# Sheet_FT4232_USB.net
KiCad netlist of a schematic drawn in Altium Designer
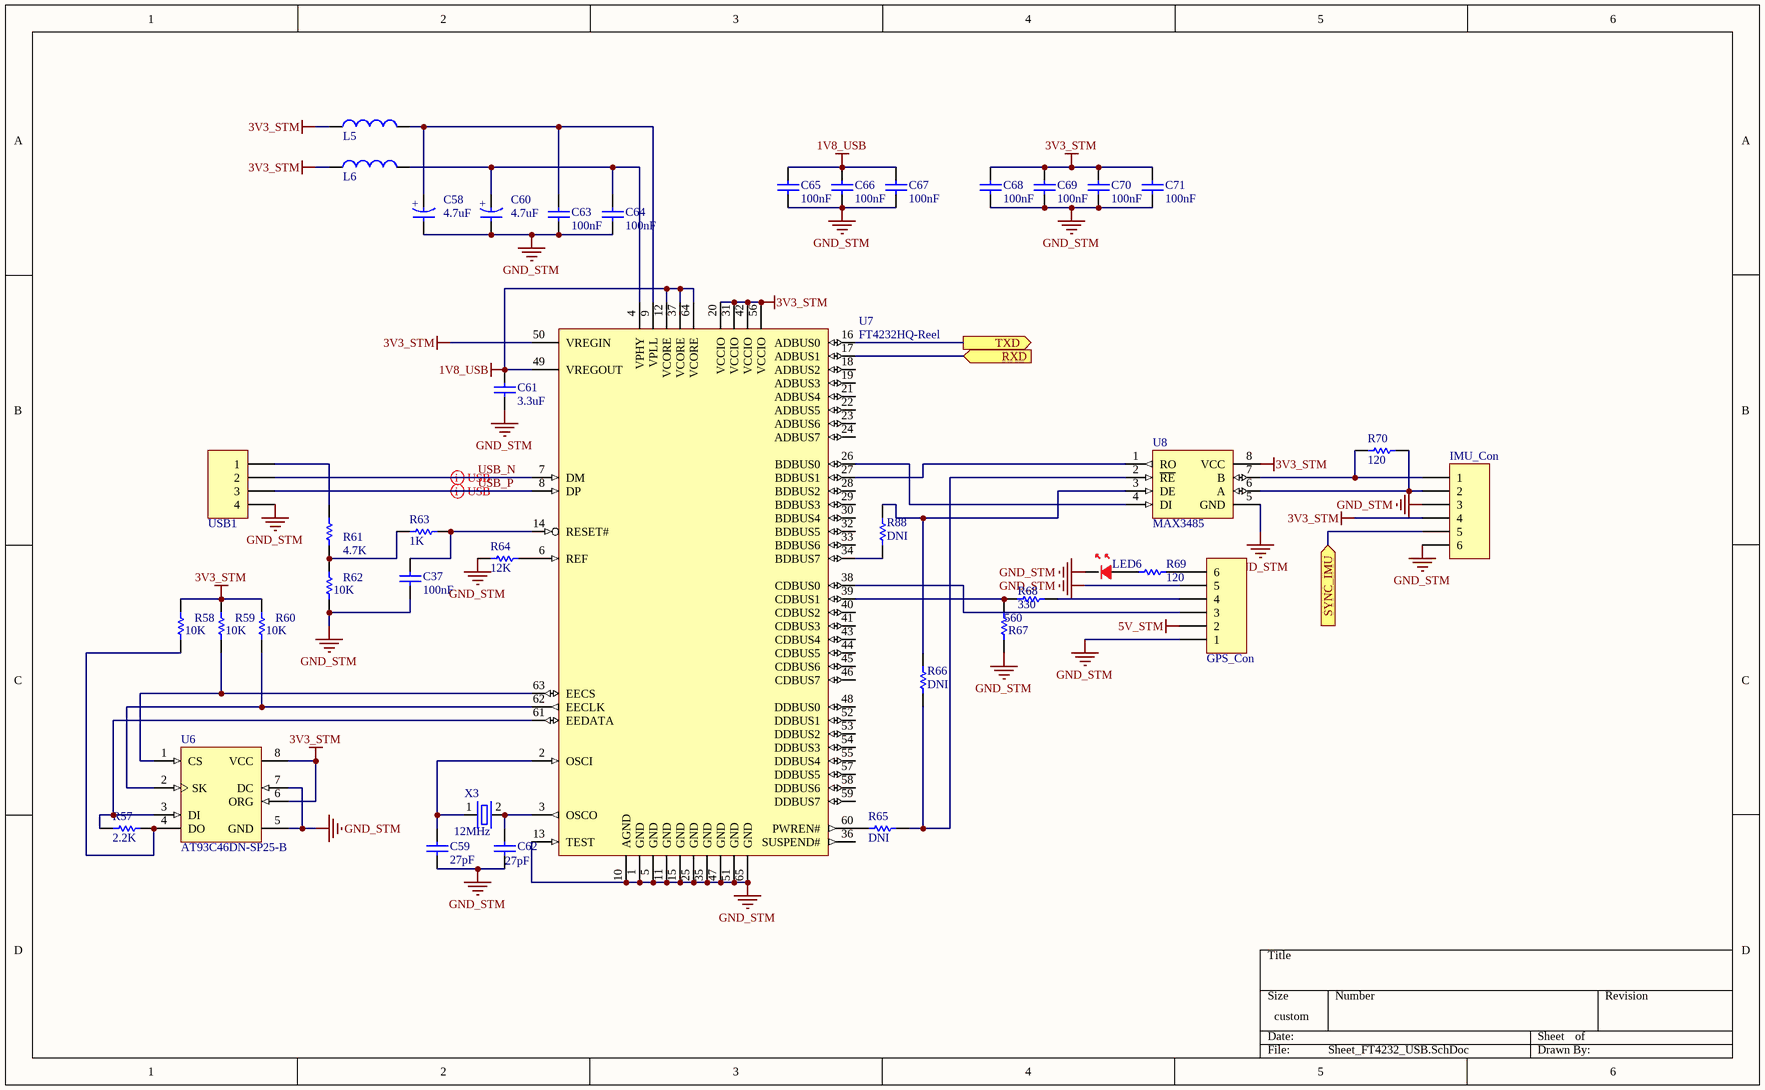
[diagram p0: Sheet_FT4232_USB.SchDoc]

(export (version "E")
  (design (tool "Eeschema 10.0.6"))
  (components
    (comp (ref "C37")
      (value "100nF")
      (footprint "ARPG_PCB_LIB:1608[0603]")
      (description "Capacitor")
      (libsource (lib "AlmaLib1") (part "Cap_BP"))
    )
    (comp (ref "C58")
      (value "4.7uF")
      (footprint "ARPG_PCB_LIB:6032 [2312]")
      (description "Capacitor")
      (libsource (lib "AlmaLib1") (part "Cap_E"))
    )
    (comp (ref "C59")
      (value "27pF")
      (footprint "ARPG_PCB_LIB:1608[0603]")
      (description "Capacitor")
      (libsource (lib "AlmaLib1") (part "Cap_BP"))
    )
    (comp (ref "C60")
      (value "4.7uF")
      (footprint "ARPG_PCB_LIB:6032 [2312]")
      (description "Capacitor")
      (libsource (lib "AlmaLib1") (part "Cap_E"))
    )
    (comp (ref "C61")
      (value "3.3uF")
      (footprint "ARPG_PCB_LIB:1608[0603]")
      (description "Capacitor")
      (libsource (lib "SchLib1") (part "Cap_BP"))
    )
    (comp (ref "C62")
      (value "27pF")
      (footprint "ARPG_PCB_LIB:1608[0603]")
      (description "Capacitor")
      (libsource (lib "AlmaLib1") (part "Cap_BP"))
    )
    (comp (ref "C63")
      (value "100nF")
      (footprint "ARPG_PCB_LIB:1608[0603]")
      (description "Capacitor")
      (libsource (lib "AlmaLib1") (part "Cap_BP"))
    )
    (comp (ref "C64")
      (value "100nF")
      (footprint "ARPG_PCB_LIB:1608[0603]")
      (description "Capacitor")
      (libsource (lib "AlmaLib1") (part "Cap_BP"))
    )
    (comp (ref "C65")
      (value "100nF")
      (footprint "ARPG_PCB_LIB:1608[0603]")
      (description "Capacitor")
      (libsource (lib "AlmaLib1") (part "Cap_BP"))
    )
    (comp (ref "C66")
      (value "100nF")
      (footprint "ARPG_PCB_LIB:1608[0603]")
      (description "Capacitor")
      (libsource (lib "AlmaLib1") (part "Cap_BP"))
    )
    (comp (ref "C67")
      (value "100nF")
      (footprint "ARPG_PCB_LIB:1608[0603]")
      (description "Capacitor")
      (libsource (lib "AlmaLib1") (part "Cap_BP"))
    )
    (comp (ref "C68")
      (value "100nF")
      (footprint "ARPG_PCB_LIB:1608[0603]")
      (description "Capacitor")
      (libsource (lib "AlmaLib1") (part "Cap_BP"))
    )
    (comp (ref "C69")
      (value "100nF")
      (footprint "ARPG_PCB_LIB:1608[0603]")
      (description "Capacitor")
      (libsource (lib "AlmaLib1") (part "Cap_BP"))
    )
    (comp (ref "C70")
      (value "100nF")
      (footprint "ARPG_PCB_LIB:1608[0603]")
      (description "Capacitor")
      (libsource (lib "AlmaLib1") (part "Cap_BP"))
    )
    (comp (ref "C71")
      (value "100nF")
      (footprint "ARPG_PCB_LIB:1608[0603]")
      (description "Capacitor")
      (libsource (lib "AlmaLib1") (part "Cap_BP"))
    )
    (comp (ref "H19")
      (value "USB1")
      (footprint "ARPG_PCB_LIB:Header 4  -MolexPicoBlade")
      (libsource (lib "SchLib1") (part "Header 4"))
    )
    (comp (ref "H20")
      (value "GPS_Con")
      (footprint "ARPG_PCB_LIB:Header 6  ZH-SM4")
      (libsource (lib "") (part "Header 6_1"))
    )
    (comp (ref "H21")
      (value "IMU_Con")
      (footprint "ARPG_PCB_LIB:Header 6  -MolexPicoBlade")
      (libsource (lib "AlmaLib1") (part "Header 6"))
    )
    (comp (ref "L5")
      (value "?H")
      (footprint "ARPG_PCB_LIB:0805")
      (description "Inductor")
      (libsource (lib "AlmaLib1") (part "Inductor"))
    )
    (comp (ref "L6")
      (value "?H")
      (footprint "ARPG_PCB_LIB:0805")
      (description "Inductor")
      (libsource (lib "AlmaLib1") (part "Inductor"))
    )
    (comp (ref "LED6")
      (value "LEDR")
      (footprint "ARPG_PCB_LIB:2012[0805]")
      (description "LED")
      (libsource (lib "AlmaLib1") (part "LED_R"))
    )
    (comp (ref "R57")
      (value "2.2K")
      (footprint "ARPG_PCB_LIB:1608[0603]")
      (description "Res")
      (libsource (lib "AlmaLib1") (part "Res"))
    )
    (comp (ref "R58")
      (value "10K")
      (footprint "ARPG_PCB_LIB:1608[0603]")
      (description "Res")
      (libsource (lib "AlmaLib1") (part "Res"))
    )
    (comp (ref "R59")
      (value "10K")
      (footprint "ARPG_PCB_LIB:1608[0603]")
      (description "Res")
      (libsource (lib "AlmaLib1") (part "Res"))
    )
    (comp (ref "R60")
      (value "10K")
      (footprint "ARPG_PCB_LIB:1608[0603]")
      (description "Res")
      (libsource (lib "AlmaLib1") (part "Res"))
    )
    (comp (ref "R61")
      (value "4.7K")
      (footprint "ARPG_PCB_LIB:1608[0603]")
      (description "Res")
      (libsource (lib "AlmaLib1") (part "Res"))
    )
    (comp (ref "R62")
      (value "10K")
      (footprint "ARPG_PCB_LIB:1608[0603]")
      (description "Res")
      (libsource (lib "AlmaLib1") (part "Res"))
    )
    (comp (ref "R63")
      (value "1K")
      (footprint "ARPG_PCB_LIB:1608[0603]")
      (description "Res")
      (libsource (lib "AlmaLib1") (part "Res"))
    )
    (comp (ref "R64")
      (value "12K")
      (footprint "ARPG_PCB_LIB:1608[0603]")
      (description "Res")
      (libsource (lib "AlmaLib1") (part "Res"))
    )
    (comp (ref "R65")
      (value "DNI")
      (footprint "ARPG_PCB_LIB:1608[0603]")
      (description "Res")
      (libsource (lib "AlmaLib1") (part "Res"))
    )
    (comp (ref "R66")
      (value "DNI")
      (footprint "ARPG_PCB_LIB:1608[0603]")
      (description "Res")
      (libsource (lib "AlmaLib1") (part "Res"))
    )
    (comp (ref "R67")
      (value "560")
      (footprint "ARPG_PCB_LIB:1608[0603]")
      (description "Res")
      (libsource (lib "AlmaLib1") (part "Res"))
    )
    (comp (ref "R68")
      (value "330")
      (footprint "ARPG_PCB_LIB:1608[0603]")
      (description "Res")
      (libsource (lib "AlmaLib1") (part "Res"))
    )
    (comp (ref "R69")
      (value "120")
      (footprint "ARPG_PCB_LIB:1608[0603]")
      (description "Res")
      (libsource (lib "AlmaLib1") (part "Res"))
    )
    (comp (ref "R70")
      (value "120")
      (footprint "ARPG_PCB_LIB:1608[0603]")
      (description "Res")
      (libsource (lib "AlmaLib1") (part "Res"))
    )
    (comp (ref "R88")
      (value "DNI")
      (footprint "ARPG_PCB_LIB:1608[0603]")
      (description "Res")
      (libsource (lib "AlmaLib1") (part "Res"))
    )
    (comp (ref "U6")
      (value "AT93C46DN-SP25-B")
      (footprint "8S1_M")
      (description "1Kbit (128 x 8 or 64 x 16), 3-wire Bus Serial Automotive EEPROM, 2.5V, 8-Pin SOIC, Bulk")
      (fields (field (name "PUBLISHER") "Altium Limited"))
      (libsource (lib "Atmel Memory Serial EEPROM") (part "AT93C46DN-SP25-B"))
    )
    (comp (ref "U7")
      (value "FT4232HQ-Reel")
      (footprint "QFN64_2_L_Smaller_Holes")
      (description "Quad High Speed USB To Multipurpose UART/MPSSE IC, QFN-64, Tape and Reel")
      (fields (field (name "PUBLISHER") "Altium Limited"))
      (libsource (lib "FTDI Communication UART") (part "FT4232HQ-Reel"))
    )
    (comp (ref "U8")
      (value "MAX3485")
      (footprint "ARPG_PCB_LIB:SOIC8")
      (libsource (lib "AlmaLib1") (part "MAX3485"))
    )
    (comp (ref "X3")
      (value "12MHz")
      (footprint "ARPG_PCB_LIB:ABM7")
      (description "Crystal Oscillator")
      (fields (field (name "PUBLISHER") "Altium Limited"))
      (libsource (lib "AlmaLib1") (part "XTAL"))
    )
  )
  (nets
    (net (code "1") (name "/RXD") (class "Default")
      (node (ref "U7") (pin "17") (pinfunction "ADBUS1_17") (pintype "bidirectional"))
    )
    (net (code "2") (name "/SYNC_IMU") (class "Default")
      (node (ref "H21") (pin "5") (pinfunction "5_5") (pintype "passive"))
    )
    (net (code "3") (name "/TXD") (class "Default")
      (node (ref "U7") (pin "16") (pinfunction "ADBUS0_16") (pintype "bidirectional"))
    )
    (net (code "4") (name "/USB_N") (class "Default")
      (node (ref "H19") (pin "2") (pinfunction "2_2") (pintype "passive"))
      (node (ref "U7") (pin "7") (pinfunction "DM_7") (pintype "input"))
    )
    (net (code "5") (name "/USB_P") (class "Default")
      (node (ref "H19") (pin "3") (pinfunction "3_3") (pintype "passive"))
      (node (ref "U7") (pin "8") (pinfunction "DP_8") (pintype "input"))
    )
    (net (code "6") (name "1V8_USB") (class "Default")
      (node (ref "C61") (pin "1") (pinfunction "1_1") (pintype "passive"))
      (node (ref "C65") (pin "1") (pinfunction "1_1") (pintype "passive"))
      (node (ref "C66") (pin "1") (pinfunction "1_1") (pintype "passive"))
      (node (ref "C67") (pin "1") (pinfunction "1_1") (pintype "passive"))
      (node (ref "U7") (pin "12") (pinfunction "VCORE_12") (pintype "power_in"))
      (node (ref "U7") (pin "37") (pinfunction "VCORE_37") (pintype "power_in"))
      (node (ref "U7") (pin "49") (pinfunction "VREGOUT_49") (pintype "power_in"))
      (node (ref "U7") (pin "64") (pinfunction "VCORE_64") (pintype "power_in"))
    )
    (net (code "7") (name "3V3_STM") (class "Default")
      (node (ref "C68") (pin "1") (pinfunction "1_1") (pintype "passive"))
      (node (ref "C69") (pin "1") (pinfunction "1_1") (pintype "passive"))
      (node (ref "C70") (pin "1") (pinfunction "1_1") (pintype "passive"))
      (node (ref "C71") (pin "1") (pinfunction "1_1") (pintype "passive"))
      (node (ref "H21") (pin "4") (pinfunction "4_4") (pintype "passive"))
      (node (ref "L5") (pin "1") (pinfunction "1_1") (pintype "passive"))
      (node (ref "L6") (pin "1") (pinfunction "1_1") (pintype "passive"))
      (node (ref "R58") (pin "2") (pinfunction "2_2") (pintype "passive"))
      (node (ref "R59") (pin "2") (pinfunction "2_2") (pintype "passive"))
      (node (ref "R60") (pin "2") (pinfunction "2_2") (pintype "passive"))
      (node (ref "U6") (pin "6") (pinfunction "ORG_6") (pintype "input"))
      (node (ref "U6") (pin "8") (pinfunction "VCC_8") (pintype "power_in"))
      (node (ref "U7") (pin "20") (pinfunction "VCCIO_20") (pintype "power_in"))
      (node (ref "U7") (pin "31") (pinfunction "VCCIO_31") (pintype "power_in"))
      (node (ref "U7") (pin "42") (pinfunction "VCCIO_42") (pintype "power_in"))
      (node (ref "U7") (pin "50") (pinfunction "VREGIN_50") (pintype "power_in"))
      (node (ref "U7") (pin "56") (pinfunction "VCCIO_56") (pintype "power_in"))
      (node (ref "U8") (pin "8") (pinfunction "VCC_8") (pintype "power_in"))
    )
    (net (code "8") (name "5V_STM") (class "Default")
      (node (ref "H20") (pin "2") (pinfunction "2_2") (pintype "passive"))
    )
    (net (code "9") (name "GND_STM") (class "Default")
      (node (ref "C37") (pin "2") (pinfunction "2_2") (pintype "passive"))
      (node (ref "C58") (pin "1") (pinfunction "1_1") (pintype "passive"))
      (node (ref "C59") (pin "2") (pinfunction "2_2") (pintype "passive"))
      (node (ref "C60") (pin "1") (pinfunction "1_1") (pintype "passive"))
      (node (ref "C61") (pin "2") (pinfunction "2_2") (pintype "passive"))
      (node (ref "C62") (pin "2") (pinfunction "2_2") (pintype "passive"))
      (node (ref "C63") (pin "2") (pinfunction "2_2") (pintype "passive"))
      (node (ref "C64") (pin "2") (pinfunction "2_2") (pintype "passive"))
      (node (ref "C65") (pin "2") (pinfunction "2_2") (pintype "passive"))
      (node (ref "C66") (pin "2") (pinfunction "2_2") (pintype "passive"))
      (node (ref "C67") (pin "2") (pinfunction "2_2") (pintype "passive"))
      (node (ref "C68") (pin "2") (pinfunction "2_2") (pintype "passive"))
      (node (ref "C69") (pin "2") (pinfunction "2_2") (pintype "passive"))
      (node (ref "C70") (pin "2") (pinfunction "2_2") (pintype "passive"))
      (node (ref "C71") (pin "2") (pinfunction "2_2") (pintype "passive"))
      (node (ref "H19") (pin "4") (pinfunction "4_4") (pintype "passive"))
      (node (ref "H20") (pin "1") (pinfunction "1_1") (pintype "passive"))
      (node (ref "H20") (pin "5") (pinfunction "5_5") (pintype "passive"))
      (node (ref "H21") (pin "3") (pinfunction "3_3") (pintype "passive"))
      (node (ref "H21") (pin "6") (pinfunction "6_6") (pintype "passive"))
      (node (ref "LED6") (pin "2") (pinfunction "K_2") (pintype "passive"))
      (node (ref "R62") (pin "1") (pinfunction "1_1") (pintype "passive"))
      (node (ref "R64") (pin "2") (pinfunction "2_2") (pintype "passive"))
      (node (ref "R67") (pin "1") (pinfunction "1_1") (pintype "passive"))
      (node (ref "U6") (pin "5") (pinfunction "GND_5") (pintype "power_in"))
      (node (ref "U6") (pin "7") (pinfunction "DC_7") (pintype "input"))
      (node (ref "U7") (pin "1") (pinfunction "GND_1") (pintype "power_in"))
      (node (ref "U7") (pin "10") (pinfunction "AGND_10") (pintype "power_in"))
      (node (ref "U7") (pin "11") (pinfunction "GND_11") (pintype "power_in"))
      (node (ref "U7") (pin "13") (pinfunction "TEST_13") (pintype "input"))
      (node (ref "U7") (pin "15") (pinfunction "GND_15") (pintype "power_in"))
      (node (ref "U7") (pin "25") (pinfunction "GND_25") (pintype "power_in"))
      (node (ref "U7") (pin "35") (pinfunction "GND_35") (pintype "power_in"))
      (node (ref "U7") (pin "47") (pinfunction "GND_47") (pintype "power_in"))
      (node (ref "U7") (pin "5") (pinfunction "GND_5") (pintype "power_in"))
      (node (ref "U7") (pin "51") (pinfunction "GND_51") (pintype "power_in"))
      (node (ref "U7") (pin "65") (pinfunction "GND_65") (pintype "power_in"))
      (node (ref "U8") (pin "5") (pinfunction "GND_5") (pintype "power_in"))
    )
    (net (code "10") (name "Net-(H19-Pad1)") (class "Default")
      (node (ref "H19") (pin "1") (pinfunction "1_1") (pintype "passive"))
      (node (ref "R61") (pin "2") (pinfunction "2_2") (pintype "passive"))
    )
    (net (code "11") (name "Net-(H20-Pad4)") (class "Default")
      (node (ref "H20") (pin "4") (pinfunction "4_4") (pintype "passive"))
      (node (ref "R68") (pin "2") (pinfunction "2_2") (pintype "passive"))
    )
    (net (code "12") (name "Net-(H20-Pad6)") (class "Default")
      (node (ref "H20") (pin "6") (pinfunction "6_6") (pintype "passive"))
      (node (ref "R69") (pin "1") (pinfunction "1_1") (pintype "passive"))
    )
    (net (code "13") (name "Net-(LED6-A)") (class "Default")
      (node (ref "LED6") (pin "1") (pinfunction "A_1") (pintype "passive"))
      (node (ref "R69") (pin "2") (pinfunction "2_2") (pintype "passive"))
    )
    (net (code "14") (name "Net-(R61-Pad1)") (class "Default")
      (node (ref "R61") (pin "1") (pinfunction "1_1") (pintype "passive"))
      (node (ref "R62") (pin "2") (pinfunction "2_2") (pintype "passive"))
      (node (ref "R63") (pin "2") (pinfunction "2_2") (pintype "passive"))
    )
    (net (code "15") (name "Net-(U6-CS)") (class "Default")
      (node (ref "R59") (pin "1") (pinfunction "1_1") (pintype "passive"))
      (node (ref "U6") (pin "1") (pinfunction "CS_1") (pintype "input"))
      (node (ref "U7") (pin "63") (pinfunction "EECS_63") (pintype "bidirectional"))
    )
    (net (code "16") (name "Net-(U6-DI)") (class "Default")
      (node (ref "R57") (pin "2") (pinfunction "2_2") (pintype "passive"))
      (node (ref "U6") (pin "3") (pinfunction "DI_3") (pintype "input"))
      (node (ref "U7") (pin "61") (pinfunction "EEDATA_61") (pintype "bidirectional"))
    )
    (net (code "17") (name "Net-(U6-DO)") (class "Default")
      (node (ref "R57") (pin "1") (pinfunction "1_1") (pintype "passive"))
      (node (ref "R58") (pin "1") (pinfunction "1_1") (pintype "passive"))
      (node (ref "U6") (pin "4") (pinfunction "DO_4") (pintype "tri_state"))
    )
    (net (code "18") (name "Net-(U6-SK)") (class "Default")
      (node (ref "R60") (pin "1") (pinfunction "1_1") (pintype "passive"))
      (node (ref "U6") (pin "2") (pinfunction "SK_2") (pintype "input"))
      (node (ref "U7") (pin "62") (pinfunction "EECLK_62") (pintype "output"))
    )
    (net (code "19") (name "Net-(U7-BDBUS0)") (class "Default")
      (node (ref "U7") (pin "26") (pinfunction "BDBUS0_26") (pintype "bidirectional"))
      (node (ref "U8") (pin "4") (pinfunction "DI_4") (pintype "input"))
    )
    (net (code "20") (name "Net-(U7-BDBUS1)") (class "Default")
      (node (ref "U7") (pin "27") (pinfunction "BDBUS1_27") (pintype "bidirectional"))
      (node (ref "U8") (pin "1") (pinfunction "RO_1") (pintype "output"))
    )
    (net (code "21") (name "Net-(U7-BDBUS7)") (class "Default")
      (node (ref "R88") (pin "1") (pinfunction "1_1") (pintype "passive"))
      (node (ref "U7") (pin "34") (pinfunction "BDBUS7_34") (pintype "bidirectional"))
    )
    (net (code "22") (name "Net-(U7-CDBUS0)") (class "Default")
      (node (ref "H20") (pin "3") (pinfunction "3_3") (pintype "passive"))
      (node (ref "U7") (pin "38") (pinfunction "CDBUS0_38") (pintype "bidirectional"))
    )
    (net (code "23") (name "Net-(U7-CDBUS1)") (class "Default")
      (node (ref "R67") (pin "2") (pinfunction "2_2") (pintype "passive"))
      (node (ref "R68") (pin "1") (pinfunction "1_1") (pintype "passive"))
      (node (ref "U7") (pin "39") (pinfunction "CDBUS1_39") (pintype "bidirectional"))
    )
    (net (code "24") (name "Net-(U7-OSCI)") (class "Default")
      (node (ref "C59") (pin "1") (pinfunction "1_1") (pintype "passive"))
      (node (ref "U7") (pin "2") (pinfunction "OSCI_2") (pintype "input"))
      (node (ref "X3") (pin "1") (pinfunction "OSC1_1") (pintype "passive"))
    )
    (net (code "25") (name "Net-(U7-OSCO)") (class "Default")
      (node (ref "C62") (pin "1") (pinfunction "1_1") (pintype "passive"))
      (node (ref "U7") (pin "3") (pinfunction "OSCO_3") (pintype "output"))
      (node (ref "X3") (pin "2") (pinfunction "OSC2_2") (pintype "passive"))
    )
    (net (code "26") (name "Net-(U7-PWREN#)") (class "Default")
      (node (ref "R65") (pin "1") (pinfunction "1_1") (pintype "passive"))
      (node (ref "U7") (pin "60") (pinfunction "PWREN#_60") (pintype "output"))
    )
    (net (code "27") (name "Net-(U7-REF)") (class "Default")
      (node (ref "R64") (pin "1") (pinfunction "1_1") (pintype "passive"))
      (node (ref "U7") (pin "6") (pinfunction "REF_6") (pintype "input"))
    )
    (net (code "28") (name "Net-(U7-RESET#)") (class "Default")
      (node (ref "C37") (pin "1") (pinfunction "1_1") (pintype "passive"))
      (node (ref "R63") (pin "1") (pinfunction "1_1") (pintype "passive"))
      (node (ref "U7") (pin "14") (pinfunction "RESET#_14") (pintype "input"))
    )
    (net (code "29") (name "Net-(U7-VPHY)") (class "Default")
      (node (ref "C60") (pin "2") (pinfunction "2_2") (pintype "passive"))
      (node (ref "C64") (pin "1") (pinfunction "1_1") (pintype "passive"))
      (node (ref "L6") (pin "2") (pinfunction "2_2") (pintype "passive"))
      (node (ref "U7") (pin "4") (pinfunction "VPHY_4") (pintype "power_in"))
    )
    (net (code "30") (name "Net-(U7-VPLL)") (class "Default")
      (node (ref "C58") (pin "2") (pinfunction "2_2") (pintype "passive"))
      (node (ref "C63") (pin "1") (pinfunction "1_1") (pintype "passive"))
      (node (ref "L5") (pin "2") (pinfunction "2_2") (pintype "passive"))
      (node (ref "U7") (pin "9") (pinfunction "VPLL_9") (pintype "power_in"))
    )
    (net (code "31") (name "Net-(U8-A)") (class "Default")
      (node (ref "H21") (pin "2") (pinfunction "2_2") (pintype "passive"))
      (node (ref "R70") (pin "1") (pinfunction "1_1") (pintype "passive"))
      (node (ref "U8") (pin "6") (pinfunction "A_6") (pintype "bidirectional"))
    )
    (net (code "32") (name "Net-(U8-B)") (class "Default")
      (node (ref "H21") (pin "1") (pinfunction "1_1") (pintype "passive"))
      (node (ref "R70") (pin "2") (pinfunction "2_2") (pintype "passive"))
      (node (ref "U8") (pin "7") (pinfunction "B_7") (pintype "bidirectional"))
    )
    (net (code "33") (name "Net-(U8-DE)") (class "Default")
      (node (ref "R66") (pin "1") (pinfunction "1_1") (pintype "passive"))
      (node (ref "R88") (pin "2") (pinfunction "2_2") (pintype "passive"))
      (node (ref "U8") (pin "3") (pinfunction "DE_3") (pintype "input"))
    )
    (net (code "34") (name "Net-(U8-~{RE})") (class "Default")
      (node (ref "R65") (pin "2") (pinfunction "2_2") (pintype "passive"))
      (node (ref "R66") (pin "2") (pinfunction "2_2") (pintype "passive"))
      (node (ref "U8") (pin "2") (pinfunction "~{RE}_2") (pintype "input"))
    )
    (net (code "35") (name "unconnected-(U7-ADBUS2-Pad18)") (class "Default")
      (node (ref "U7") (pin "18") (pinfunction "ADBUS2_18") (pintype "bidirectional"))
    )
    (net (code "36") (name "unconnected-(U7-ADBUS3-Pad19)") (class "Default")
      (node (ref "U7") (pin "19") (pinfunction "ADBUS3_19") (pintype "bidirectional"))
    )
    (net (code "37") (name "unconnected-(U7-ADBUS4-Pad21)") (class "Default")
      (node (ref "U7") (pin "21") (pinfunction "ADBUS4_21") (pintype "bidirectional"))
    )
    (net (code "38") (name "unconnected-(U7-ADBUS5-Pad22)") (class "Default")
      (node (ref "U7") (pin "22") (pinfunction "ADBUS5_22") (pintype "bidirectional"))
    )
    (net (code "39") (name "unconnected-(U7-ADBUS6-Pad23)") (class "Default")
      (node (ref "U7") (pin "23") (pinfunction "ADBUS6_23") (pintype "bidirectional"))
    )
    (net (code "40") (name "unconnected-(U7-ADBUS7-Pad24)") (class "Default")
      (node (ref "U7") (pin "24") (pinfunction "ADBUS7_24") (pintype "bidirectional"))
    )
    (net (code "41") (name "unconnected-(U7-BDBUS2-Pad28)") (class "Default")
      (node (ref "U7") (pin "28") (pinfunction "BDBUS2_28") (pintype "bidirectional"))
    )
    (net (code "42") (name "unconnected-(U7-BDBUS3-Pad29)") (class "Default")
      (node (ref "U7") (pin "29") (pinfunction "BDBUS3_29") (pintype "bidirectional"))
    )
    (net (code "43") (name "unconnected-(U7-BDBUS4-Pad30)") (class "Default")
      (node (ref "U7") (pin "30") (pinfunction "BDBUS4_30") (pintype "bidirectional"))
    )
    (net (code "44") (name "unconnected-(U7-BDBUS5-Pad32)") (class "Default")
      (node (ref "U7") (pin "32") (pinfunction "BDBUS5_32") (pintype "bidirectional"))
    )
    (net (code "45") (name "unconnected-(U7-BDBUS6-Pad33)") (class "Default")
      (node (ref "U7") (pin "33") (pinfunction "BDBUS6_33") (pintype "bidirectional"))
    )
    (net (code "46") (name "unconnected-(U7-CDBUS2-Pad40)") (class "Default")
      (node (ref "U7") (pin "40") (pinfunction "CDBUS2_40") (pintype "bidirectional"))
    )
    (net (code "47") (name "unconnected-(U7-CDBUS3-Pad41)") (class "Default")
      (node (ref "U7") (pin "41") (pinfunction "CDBUS3_41") (pintype "bidirectional"))
    )
    (net (code "48") (name "unconnected-(U7-CDBUS4-Pad43)") (class "Default")
      (node (ref "U7") (pin "43") (pinfunction "CDBUS4_43") (pintype "bidirectional"))
    )
    (net (code "49") (name "unconnected-(U7-CDBUS5-Pad44)") (class "Default")
      (node (ref "U7") (pin "44") (pinfunction "CDBUS5_44") (pintype "bidirectional"))
    )
    (net (code "50") (name "unconnected-(U7-CDBUS6-Pad45)") (class "Default")
      (node (ref "U7") (pin "45") (pinfunction "CDBUS6_45") (pintype "bidirectional"))
    )
    (net (code "51") (name "unconnected-(U7-CDBUS7-Pad46)") (class "Default")
      (node (ref "U7") (pin "46") (pinfunction "CDBUS7_46") (pintype "bidirectional"))
    )
    (net (code "52") (name "unconnected-(U7-DDBUS0-Pad48)") (class "Default")
      (node (ref "U7") (pin "48") (pinfunction "DDBUS0_48") (pintype "bidirectional"))
    )
    (net (code "53") (name "unconnected-(U7-DDBUS1-Pad52)") (class "Default")
      (node (ref "U7") (pin "52") (pinfunction "DDBUS1_52") (pintype "bidirectional"))
    )
    (net (code "54") (name "unconnected-(U7-DDBUS2-Pad53)") (class "Default")
      (node (ref "U7") (pin "53") (pinfunction "DDBUS2_53") (pintype "bidirectional"))
    )
    (net (code "55") (name "unconnected-(U7-DDBUS3-Pad54)") (class "Default")
      (node (ref "U7") (pin "54") (pinfunction "DDBUS3_54") (pintype "bidirectional"))
    )
    (net (code "56") (name "unconnected-(U7-DDBUS4-Pad55)") (class "Default")
      (node (ref "U7") (pin "55") (pinfunction "DDBUS4_55") (pintype "bidirectional"))
    )
    (net (code "57") (name "unconnected-(U7-DDBUS5-Pad57)") (class "Default")
      (node (ref "U7") (pin "57") (pinfunction "DDBUS5_57") (pintype "bidirectional"))
    )
    (net (code "58") (name "unconnected-(U7-DDBUS6-Pad58)") (class "Default")
      (node (ref "U7") (pin "58") (pinfunction "DDBUS6_58") (pintype "bidirectional"))
    )
    (net (code "59") (name "unconnected-(U7-DDBUS7-Pad59)") (class "Default")
      (node (ref "U7") (pin "59") (pinfunction "DDBUS7_59") (pintype "bidirectional"))
    )
    (net (code "60") (name "unconnected-(U7-SUSPEND#-Pad36)") (class "Default")
      (node (ref "U7") (pin "36") (pinfunction "SUSPEND#_36") (pintype "output"))
    )
  )
)
